# ShiftRegister.net
KiCad netlist of a schematic drawn in Altium Designer
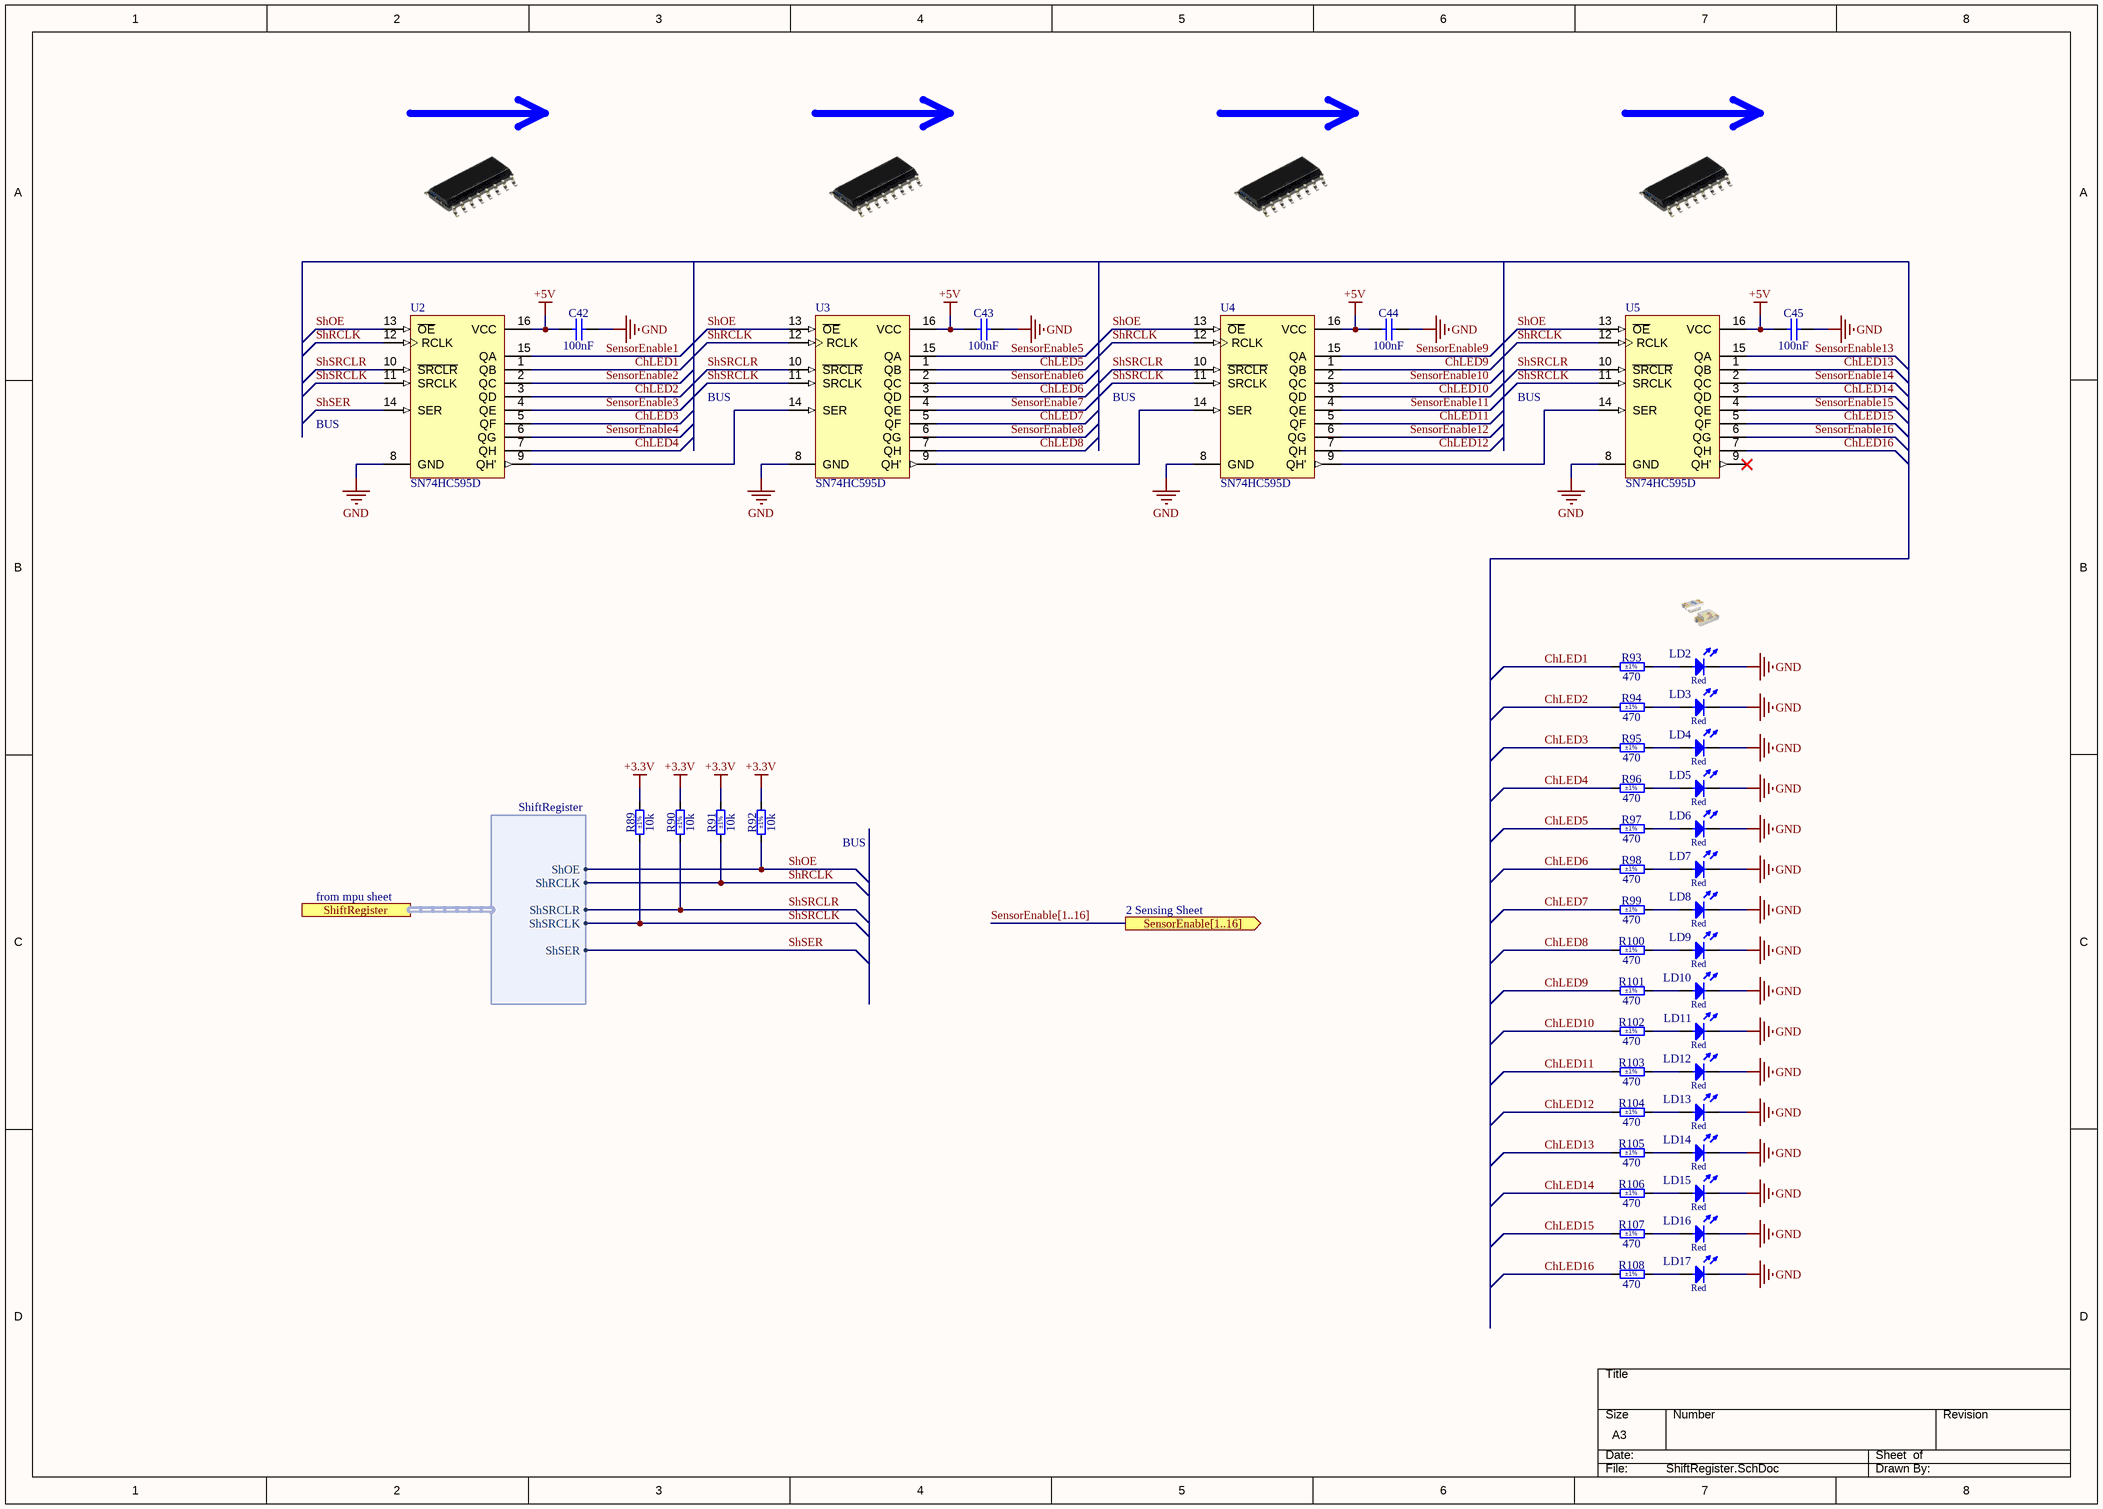
[diagram p0: ShiftRegister.SchDoc]

(export (version "E")
  (design (tool "Eeschema 10.0.6"))
  (components
    (comp (ref "C42")
      (value "100nF")
      (footprint "CAPC1608X87N")
      (description "Non-polarised capacitor")
      (fields
        (field (name "PART NUMBER") "CC0603_100NF_50V_10%_X7R")
        (field (name "VOLTAGE") "50V")
        (field (name "AUTHOR") "CERN DEM JLC")
      )
      (libsource (lib "Capacitors") (part "Capacitor - non polarized"))
    )
    (comp (ref "C43")
      (value "100nF")
      (footprint "CAPC1608X87N")
      (description "Non-polarised capacitor")
      (fields
        (field (name "PART NUMBER") "CC0603_100NF_50V_10%_X7R")
        (field (name "VOLTAGE") "50V")
        (field (name "AUTHOR") "CERN DEM JLC")
      )
      (libsource (lib "Capacitors") (part "Capacitor - non polarized"))
    )
    (comp (ref "C44")
      (value "100nF")
      (footprint "CAPC1608X87N")
      (description "Non-polarised capacitor")
      (fields
        (field (name "PART NUMBER") "CC0603_100NF_50V_10%_X7R")
        (field (name "VOLTAGE") "50V")
        (field (name "AUTHOR") "CERN DEM JLC")
      )
      (libsource (lib "Capacitors") (part "Capacitor - non polarized"))
    )
    (comp (ref "C45")
      (value "100nF")
      (footprint "CAPC1608X87N")
      (description "Non-polarised capacitor")
      (fields
        (field (name "PART NUMBER") "CC0603_100NF_50V_10%_X7R")
        (field (name "VOLTAGE") "50V")
        (field (name "AUTHOR") "CERN DEM JLC")
      )
      (libsource (lib "Capacitors") (part "Capacitor - non polarized"))
    )
    (comp (ref "LD2")
      (value "Red")
      (footprint "LED_AVAGO_HSMH-C150")
      (description "LED Red 1C 2A")
      (fields
        (field (name "PART NUMBER") "LED_AVAGO_HSMH-C150")
        (field (name "MANUFACTURER") "AVAGO TECHNOLOGIES")
        (field (name "AUTHOR") "CERN DEM JLC")
      )
      (libsource (lib "ICs And Semiconductors") (part "LED Red 1C 2A"))
    )
    (comp (ref "LD3")
      (value "Red")
      (footprint "LED_AVAGO_HSMH-C150")
      (description "LED Red 1C 2A")
      (fields
        (field (name "PART NUMBER") "LED_AVAGO_HSMH-C150")
        (field (name "MANUFACTURER") "AVAGO TECHNOLOGIES")
        (field (name "AUTHOR") "CERN DEM JLC")
      )
      (libsource (lib "ICs And Semiconductors") (part "LED Red 1C 2A"))
    )
    (comp (ref "LD4")
      (value "Red")
      (footprint "LED_AVAGO_HSMH-C150")
      (description "LED Red 1C 2A")
      (fields
        (field (name "PART NUMBER") "LED_AVAGO_HSMH-C150")
        (field (name "MANUFACTURER") "AVAGO TECHNOLOGIES")
        (field (name "AUTHOR") "CERN DEM JLC")
      )
      (libsource (lib "ICs And Semiconductors") (part "LED Red 1C 2A"))
    )
    (comp (ref "LD5")
      (value "Red")
      (footprint "LED_AVAGO_HSMH-C150")
      (description "LED Red 1C 2A")
      (fields
        (field (name "PART NUMBER") "LED_AVAGO_HSMH-C150")
        (field (name "MANUFACTURER") "AVAGO TECHNOLOGIES")
        (field (name "AUTHOR") "CERN DEM JLC")
      )
      (libsource (lib "ICs And Semiconductors") (part "LED Red 1C 2A"))
    )
    (comp (ref "LD6")
      (value "Red")
      (footprint "LED_AVAGO_HSMH-C150")
      (description "LED Red 1C 2A")
      (fields
        (field (name "PART NUMBER") "LED_AVAGO_HSMH-C150")
        (field (name "MANUFACTURER") "AVAGO TECHNOLOGIES")
        (field (name "AUTHOR") "CERN DEM JLC")
      )
      (libsource (lib "ICs And Semiconductors") (part "LED Red 1C 2A"))
    )
    (comp (ref "LD7")
      (value "Red")
      (footprint "LED_AVAGO_HSMH-C150")
      (description "LED Red 1C 2A")
      (fields
        (field (name "PART NUMBER") "LED_AVAGO_HSMH-C150")
        (field (name "MANUFACTURER") "AVAGO TECHNOLOGIES")
        (field (name "AUTHOR") "CERN DEM JLC")
      )
      (libsource (lib "ICs And Semiconductors") (part "LED Red 1C 2A"))
    )
    (comp (ref "LD8")
      (value "Red")
      (footprint "LED_AVAGO_HSMH-C150")
      (description "LED Red 1C 2A")
      (fields
        (field (name "PART NUMBER") "LED_AVAGO_HSMH-C150")
        (field (name "MANUFACTURER") "AVAGO TECHNOLOGIES")
        (field (name "AUTHOR") "CERN DEM JLC")
      )
      (libsource (lib "ICs And Semiconductors") (part "LED Red 1C 2A"))
    )
    (comp (ref "LD9")
      (value "Red")
      (footprint "LED_AVAGO_HSMH-C150")
      (description "LED Red 1C 2A")
      (fields
        (field (name "PART NUMBER") "LED_AVAGO_HSMH-C150")
        (field (name "MANUFACTURER") "AVAGO TECHNOLOGIES")
        (field (name "AUTHOR") "CERN DEM JLC")
      )
      (libsource (lib "ICs And Semiconductors") (part "LED Red 1C 2A"))
    )
    (comp (ref "LD10")
      (value "Red")
      (footprint "LED_AVAGO_HSMH-C150")
      (description "LED Red 1C 2A")
      (fields
        (field (name "PART NUMBER") "LED_AVAGO_HSMH-C150")
        (field (name "MANUFACTURER") "AVAGO TECHNOLOGIES")
        (field (name "AUTHOR") "CERN DEM JLC")
      )
      (libsource (lib "ICs And Semiconductors") (part "LED Red 1C 2A"))
    )
    (comp (ref "LD11")
      (value "Red")
      (footprint "LED_AVAGO_HSMH-C150")
      (description "LED Red 1C 2A")
      (fields
        (field (name "PART NUMBER") "LED_AVAGO_HSMH-C150")
        (field (name "MANUFACTURER") "AVAGO TECHNOLOGIES")
        (field (name "AUTHOR") "CERN DEM JLC")
      )
      (libsource (lib "ICs And Semiconductors") (part "LED Red 1C 2A"))
    )
    (comp (ref "LD12")
      (value "Red")
      (footprint "LED_AVAGO_HSMH-C150")
      (description "LED Red 1C 2A")
      (fields
        (field (name "PART NUMBER") "LED_AVAGO_HSMH-C150")
        (field (name "MANUFACTURER") "AVAGO TECHNOLOGIES")
        (field (name "AUTHOR") "CERN DEM JLC")
      )
      (libsource (lib "ICs And Semiconductors") (part "LED Red 1C 2A"))
    )
    (comp (ref "LD13")
      (value "Red")
      (footprint "LED_AVAGO_HSMH-C150")
      (description "LED Red 1C 2A")
      (fields
        (field (name "PART NUMBER") "LED_AVAGO_HSMH-C150")
        (field (name "MANUFACTURER") "AVAGO TECHNOLOGIES")
        (field (name "AUTHOR") "CERN DEM JLC")
      )
      (libsource (lib "ICs And Semiconductors") (part "LED Red 1C 2A"))
    )
    (comp (ref "LD14")
      (value "Red")
      (footprint "LED_AVAGO_HSMH-C150")
      (description "LED Red 1C 2A")
      (fields
        (field (name "PART NUMBER") "LED_AVAGO_HSMH-C150")
        (field (name "MANUFACTURER") "AVAGO TECHNOLOGIES")
        (field (name "AUTHOR") "CERN DEM JLC")
      )
      (libsource (lib "ICs And Semiconductors") (part "LED Red 1C 2A"))
    )
    (comp (ref "LD15")
      (value "Red")
      (footprint "LED_AVAGO_HSMH-C150")
      (description "LED Red 1C 2A")
      (fields
        (field (name "PART NUMBER") "LED_AVAGO_HSMH-C150")
        (field (name "MANUFACTURER") "AVAGO TECHNOLOGIES")
        (field (name "AUTHOR") "CERN DEM JLC")
      )
      (libsource (lib "ICs And Semiconductors") (part "LED Red 1C 2A"))
    )
    (comp (ref "LD16")
      (value "Red")
      (footprint "LED_AVAGO_HSMH-C150")
      (description "LED Red 1C 2A")
      (fields
        (field (name "PART NUMBER") "LED_AVAGO_HSMH-C150")
        (field (name "MANUFACTURER") "AVAGO TECHNOLOGIES")
        (field (name "AUTHOR") "CERN DEM JLC")
      )
      (libsource (lib "ICs And Semiconductors") (part "LED Red 1C 2A"))
    )
    (comp (ref "LD17")
      (value "Red")
      (footprint "LED_AVAGO_HSMH-C150")
      (description "LED Red 1C 2A")
      (fields
        (field (name "PART NUMBER") "LED_AVAGO_HSMH-C150")
        (field (name "MANUFACTURER") "AVAGO TECHNOLOGIES")
        (field (name "AUTHOR") "CERN DEM JLC")
      )
      (libsource (lib "ICs And Semiconductors") (part "LED Red 1C 2A"))
    )
    (comp (ref "R89")
      (value "10k")
      (footprint "RESC1608X55N")
      (description "Resistor - 1%")
      (fields
        (field (name "TOLERANCE") "±1%")
        (field (name "PART NUMBER") "R0603_10K_1%_0.1W_100PPM")
        (field (name "POWER") "0.1W")
        (field (name "AUTHOR") "CERN DEM JLC")
      )
      (libsource (lib "Resistors") (part "Resistor - 1%"))
    )
    (comp (ref "R90")
      (value "10k")
      (footprint "RESC1608X55N")
      (description "Resistor - 1%")
      (fields
        (field (name "TOLERANCE") "±1%")
        (field (name "PART NUMBER") "R0603_10K_1%_0.1W_100PPM")
        (field (name "POWER") "0.1W")
        (field (name "AUTHOR") "CERN DEM JLC")
      )
      (libsource (lib "Resistors") (part "Resistor - 1%"))
    )
    (comp (ref "R91")
      (value "10k")
      (footprint "RESC1608X55N")
      (description "Resistor - 1%")
      (fields
        (field (name "TOLERANCE") "±1%")
        (field (name "PART NUMBER") "R0603_10K_1%_0.1W_100PPM")
        (field (name "POWER") "0.1W")
        (field (name "AUTHOR") "CERN DEM JLC")
      )
      (libsource (lib "Resistors") (part "Resistor - 1%"))
    )
    (comp (ref "R92")
      (value "10k")
      (footprint "RESC1608X55N")
      (description "Resistor - 1%")
      (fields
        (field (name "TOLERANCE") "±1%")
        (field (name "PART NUMBER") "R0603_10K_1%_0.1W_100PPM")
        (field (name "POWER") "0.1W")
        (field (name "AUTHOR") "CERN DEM JLC")
      )
      (libsource (lib "Resistors") (part "Resistor - 1%"))
    )
    (comp (ref "R93")
      (value "470")
      (footprint "RESC1608X55N")
      (description "Resistor - 1%")
      (fields
        (field (name "TOLERANCE") "±1%")
        (field (name "PART NUMBER") "R0603_470R_1%_0.1W_100PPM")
        (field (name "POWER") "0.1W")
        (field (name "AUTHOR") "CERN DEM JLC")
      )
      (libsource (lib "Resistors") (part "Resistor - 1%"))
    )
    (comp (ref "R94")
      (value "470")
      (footprint "RESC1608X55N")
      (description "Resistor - 1%")
      (fields
        (field (name "TOLERANCE") "±1%")
        (field (name "PART NUMBER") "R0603_470R_1%_0.1W_100PPM")
        (field (name "POWER") "0.1W")
        (field (name "AUTHOR") "CERN DEM JLC")
      )
      (libsource (lib "Resistors") (part "Resistor - 1%"))
    )
    (comp (ref "R95")
      (value "470")
      (footprint "RESC1608X55N")
      (description "Resistor - 1%")
      (fields
        (field (name "TOLERANCE") "±1%")
        (field (name "PART NUMBER") "R0603_470R_1%_0.1W_100PPM")
        (field (name "POWER") "0.1W")
        (field (name "AUTHOR") "CERN DEM JLC")
      )
      (libsource (lib "Resistors") (part "Resistor - 1%"))
    )
    (comp (ref "R96")
      (value "470")
      (footprint "RESC1608X55N")
      (description "Resistor - 1%")
      (fields
        (field (name "TOLERANCE") "±1%")
        (field (name "PART NUMBER") "R0603_470R_1%_0.1W_100PPM")
        (field (name "POWER") "0.1W")
        (field (name "AUTHOR") "CERN DEM JLC")
      )
      (libsource (lib "Resistors") (part "Resistor - 1%"))
    )
    (comp (ref "R97")
      (value "470")
      (footprint "RESC1608X55N")
      (description "Resistor - 1%")
      (fields
        (field (name "TOLERANCE") "±1%")
        (field (name "PART NUMBER") "R0603_470R_1%_0.1W_100PPM")
        (field (name "POWER") "0.1W")
        (field (name "AUTHOR") "CERN DEM JLC")
      )
      (libsource (lib "Resistors") (part "Resistor - 1%"))
    )
    (comp (ref "R98")
      (value "470")
      (footprint "RESC1608X55N")
      (description "Resistor - 1%")
      (fields
        (field (name "TOLERANCE") "±1%")
        (field (name "PART NUMBER") "R0603_470R_1%_0.1W_100PPM")
        (field (name "POWER") "0.1W")
        (field (name "AUTHOR") "CERN DEM JLC")
      )
      (libsource (lib "Resistors") (part "Resistor - 1%"))
    )
    (comp (ref "R99")
      (value "470")
      (footprint "RESC1608X55N")
      (description "Resistor - 1%")
      (fields
        (field (name "TOLERANCE") "±1%")
        (field (name "PART NUMBER") "R0603_470R_1%_0.1W_100PPM")
        (field (name "POWER") "0.1W")
        (field (name "AUTHOR") "CERN DEM JLC")
      )
      (libsource (lib "Resistors") (part "Resistor - 1%"))
    )
    (comp (ref "R100")
      (value "470")
      (footprint "RESC1608X55N")
      (description "Resistor - 1%")
      (fields
        (field (name "TOLERANCE") "±1%")
        (field (name "PART NUMBER") "R0603_470R_1%_0.1W_100PPM")
        (field (name "POWER") "0.1W")
        (field (name "AUTHOR") "CERN DEM JLC")
      )
      (libsource (lib "Resistors") (part "Resistor - 1%"))
    )
    (comp (ref "R101")
      (value "470")
      (footprint "RESC1608X55N")
      (description "Resistor - 1%")
      (fields
        (field (name "TOLERANCE") "±1%")
        (field (name "PART NUMBER") "R0603_470R_1%_0.1W_100PPM")
        (field (name "POWER") "0.1W")
        (field (name "AUTHOR") "CERN DEM JLC")
      )
      (libsource (lib "Resistors") (part "Resistor - 1%"))
    )
    (comp (ref "R102")
      (value "470")
      (footprint "RESC1608X55N")
      (description "Resistor - 1%")
      (fields
        (field (name "TOLERANCE") "±1%")
        (field (name "PART NUMBER") "R0603_470R_1%_0.1W_100PPM")
        (field (name "POWER") "0.1W")
        (field (name "AUTHOR") "CERN DEM JLC")
      )
      (libsource (lib "Resistors") (part "Resistor - 1%"))
    )
    (comp (ref "R103")
      (value "470")
      (footprint "RESC1608X55N")
      (description "Resistor - 1%")
      (fields
        (field (name "TOLERANCE") "±1%")
        (field (name "PART NUMBER") "R0603_470R_1%_0.1W_100PPM")
        (field (name "POWER") "0.1W")
        (field (name "AUTHOR") "CERN DEM JLC")
      )
      (libsource (lib "Resistors") (part "Resistor - 1%"))
    )
    (comp (ref "R104")
      (value "470")
      (footprint "RESC1608X55N")
      (description "Resistor - 1%")
      (fields
        (field (name "TOLERANCE") "±1%")
        (field (name "PART NUMBER") "R0603_470R_1%_0.1W_100PPM")
        (field (name "POWER") "0.1W")
        (field (name "AUTHOR") "CERN DEM JLC")
      )
      (libsource (lib "Resistors") (part "Resistor - 1%"))
    )
    (comp (ref "R105")
      (value "470")
      (footprint "RESC1608X55N")
      (description "Resistor - 1%")
      (fields
        (field (name "TOLERANCE") "±1%")
        (field (name "PART NUMBER") "R0603_470R_1%_0.1W_100PPM")
        (field (name "POWER") "0.1W")
        (field (name "AUTHOR") "CERN DEM JLC")
      )
      (libsource (lib "Resistors") (part "Resistor - 1%"))
    )
    (comp (ref "R106")
      (value "470")
      (footprint "RESC1608X55N")
      (description "Resistor - 1%")
      (fields
        (field (name "TOLERANCE") "±1%")
        (field (name "PART NUMBER") "R0603_470R_1%_0.1W_100PPM")
        (field (name "POWER") "0.1W")
        (field (name "AUTHOR") "CERN DEM JLC")
      )
      (libsource (lib "Resistors") (part "Resistor - 1%"))
    )
    (comp (ref "R107")
      (value "470")
      (footprint "RESC1608X55N")
      (description "Resistor - 1%")
      (fields
        (field (name "TOLERANCE") "±1%")
        (field (name "PART NUMBER") "R0603_470R_1%_0.1W_100PPM")
        (field (name "POWER") "0.1W")
        (field (name "AUTHOR") "CERN DEM JLC")
      )
      (libsource (lib "Resistors") (part "Resistor - 1%"))
    )
    (comp (ref "R108")
      (value "470")
      (footprint "RESC1608X55N")
      (description "Resistor - 1%")
      (fields
        (field (name "TOLERANCE") "±1%")
        (field (name "PART NUMBER") "R0603_470R_1%_0.1W_100PPM")
        (field (name "POWER") "0.1W")
        (field (name "AUTHOR") "CERN DEM JLC")
      )
      (libsource (lib "Resistors") (part "Resistor - 1%"))
    )
    (comp (ref "U2")
      (value "SN74HC595D")
      (footprint "SO16")
      (description "8-Bit Shift Register with 3-State Output Registers")
      (fields (field (name "PUBLISHER") "Altium Limited"))
      (libsource (lib "Sajad_Altium_Library") (part "SN74HC595D"))
    )
    (comp (ref "U3")
      (value "SN74HC595D")
      (footprint "SO16")
      (description "8-Bit Shift Register with 3-State Output Registers")
      (fields (field (name "PUBLISHER") "Altium Limited"))
      (libsource (lib "Sajad_Altium_Library") (part "SN74HC595D"))
    )
    (comp (ref "U4")
      (value "SN74HC595D")
      (footprint "SO16")
      (description "8-Bit Shift Register with 3-State Output Registers")
      (fields (field (name "PUBLISHER") "Altium Limited"))
      (libsource (lib "Sajad_Altium_Library") (part "SN74HC595D"))
    )
    (comp (ref "U5")
      (value "SN74HC595D")
      (footprint "SO16")
      (description "8-Bit Shift Register with 3-State Output Registers")
      (fields (field (name "PUBLISHER") "Altium Limited"))
      (libsource (lib "Sajad_Altium_Library") (part "SN74HC595D"))
    )
  )
  (nets
    (net (code "2") (name "+3.3V") (class "Default")
      (node (ref "R89") (pin "2") (pinfunction "2_2") (pintype "passive"))
      (node (ref "R90") (pin "2") (pinfunction "2_2") (pintype "passive"))
      (node (ref "R91") (pin "2") (pinfunction "2_2") (pintype "passive"))
      (node (ref "R92") (pin "2") (pinfunction "2_2") (pintype "passive"))
    )
    (net (code "3") (name "+5V") (class "Default")
      (node (ref "C42") (pin "1") (pinfunction "1_1") (pintype "passive"))
      (node (ref "C43") (pin "1") (pinfunction "1_1") (pintype "passive"))
      (node (ref "C44") (pin "1") (pinfunction "1_1") (pintype "passive"))
      (node (ref "C45") (pin "1") (pinfunction "1_1") (pintype "passive"))
      (node (ref "U2") (pin "16") (pinfunction "VCC_16") (pintype "power_in"))
      (node (ref "U3") (pin "16") (pinfunction "VCC_16") (pintype "power_in"))
      (node (ref "U4") (pin "16") (pinfunction "VCC_16") (pintype "power_in"))
      (node (ref "U5") (pin "16") (pinfunction "VCC_16") (pintype "power_in"))
    )
    (net (code "4") (name "/ChLED1") (class "Default")
      (node (ref "R93") (pin "1") (pinfunction "1_1") (pintype "passive"))
      (node (ref "U2") (pin "1") (pinfunction "QB_1") (pintype "tri_state"))
    )
    (net (code "5") (name "/ChLED2") (class "Default")
      (node (ref "R94") (pin "1") (pinfunction "1_1") (pintype "passive"))
      (node (ref "U2") (pin "3") (pinfunction "QD_3") (pintype "tri_state"))
    )
    (net (code "6") (name "/ChLED3") (class "Default")
      (node (ref "R95") (pin "1") (pinfunction "1_1") (pintype "passive"))
      (node (ref "U2") (pin "5") (pinfunction "QF_5") (pintype "tri_state"))
    )
    (net (code "7") (name "/ChLED4") (class "Default")
      (node (ref "R96") (pin "1") (pinfunction "1_1") (pintype "passive"))
      (node (ref "U2") (pin "7") (pinfunction "QH_7") (pintype "tri_state"))
    )
    (net (code "8") (name "/ChLED5") (class "Default")
      (node (ref "R97") (pin "1") (pinfunction "1_1") (pintype "passive"))
      (node (ref "U3") (pin "1") (pinfunction "QB_1") (pintype "tri_state"))
    )
    (net (code "9") (name "/ChLED6") (class "Default")
      (node (ref "R98") (pin "1") (pinfunction "1_1") (pintype "passive"))
      (node (ref "U3") (pin "3") (pinfunction "QD_3") (pintype "tri_state"))
    )
    (net (code "10") (name "/ChLED7") (class "Default")
      (node (ref "R99") (pin "1") (pinfunction "1_1") (pintype "passive"))
      (node (ref "U3") (pin "5") (pinfunction "QF_5") (pintype "tri_state"))
    )
    (net (code "11") (name "/ChLED8") (class "Default")
      (node (ref "R100") (pin "1") (pinfunction "1_1") (pintype "passive"))
      (node (ref "U3") (pin "7") (pinfunction "QH_7") (pintype "tri_state"))
    )
    (net (code "12") (name "/ChLED9") (class "Default")
      (node (ref "R101") (pin "1") (pinfunction "1_1") (pintype "passive"))
      (node (ref "U4") (pin "1") (pinfunction "QB_1") (pintype "tri_state"))
    )
    (net (code "13") (name "/ChLED10") (class "Default")
      (node (ref "R102") (pin "1") (pinfunction "1_1") (pintype "passive"))
      (node (ref "U4") (pin "3") (pinfunction "QD_3") (pintype "tri_state"))
    )
    (net (code "14") (name "/ChLED11") (class "Default")
      (node (ref "R103") (pin "1") (pinfunction "1_1") (pintype "passive"))
      (node (ref "U4") (pin "5") (pinfunction "QF_5") (pintype "tri_state"))
    )
    (net (code "15") (name "/ChLED12") (class "Default")
      (node (ref "R104") (pin "1") (pinfunction "1_1") (pintype "passive"))
      (node (ref "U4") (pin "7") (pinfunction "QH_7") (pintype "tri_state"))
    )
    (net (code "16") (name "/ChLED13") (class "Default")
      (node (ref "R105") (pin "1") (pinfunction "1_1") (pintype "passive"))
      (node (ref "U5") (pin "1") (pinfunction "QB_1") (pintype "tri_state"))
    )
    (net (code "17") (name "/ChLED14") (class "Default")
      (node (ref "R106") (pin "1") (pinfunction "1_1") (pintype "passive"))
      (node (ref "U5") (pin "3") (pinfunction "QD_3") (pintype "tri_state"))
    )
    (net (code "18") (name "/ChLED15") (class "Default")
      (node (ref "R107") (pin "1") (pinfunction "1_1") (pintype "passive"))
      (node (ref "U5") (pin "5") (pinfunction "QF_5") (pintype "tri_state"))
    )
    (net (code "19") (name "/ChLED16") (class "Default")
      (node (ref "R108") (pin "1") (pinfunction "1_1") (pintype "passive"))
      (node (ref "U5") (pin "7") (pinfunction "QH_7") (pintype "tri_state"))
    )
    (net (code "20") (name "/SensorEnable1") (class "Default")
      (node (ref "U2") (pin "15") (pinfunction "QA_15") (pintype "tri_state"))
    )
    (net (code "21") (name "/SensorEnable2") (class "Default")
      (node (ref "U2") (pin "2") (pinfunction "QC_2") (pintype "tri_state"))
    )
    (net (code "22") (name "/SensorEnable3") (class "Default")
      (node (ref "U2") (pin "4") (pinfunction "QE_4") (pintype "tri_state"))
    )
    (net (code "23") (name "/SensorEnable4") (class "Default")
      (node (ref "U2") (pin "6") (pinfunction "QG_6") (pintype "tri_state"))
    )
    (net (code "24") (name "/SensorEnable5") (class "Default")
      (node (ref "U3") (pin "15") (pinfunction "QA_15") (pintype "tri_state"))
    )
    (net (code "25") (name "/SensorEnable6") (class "Default")
      (node (ref "U3") (pin "2") (pinfunction "QC_2") (pintype "tri_state"))
    )
    (net (code "26") (name "/SensorEnable7") (class "Default")
      (node (ref "U3") (pin "4") (pinfunction "QE_4") (pintype "tri_state"))
    )
    (net (code "27") (name "/SensorEnable8") (class "Default")
      (node (ref "U3") (pin "6") (pinfunction "QG_6") (pintype "tri_state"))
    )
    (net (code "28") (name "/SensorEnable9") (class "Default")
      (node (ref "U4") (pin "15") (pinfunction "QA_15") (pintype "tri_state"))
    )
    (net (code "29") (name "/SensorEnable10") (class "Default")
      (node (ref "U4") (pin "2") (pinfunction "QC_2") (pintype "tri_state"))
    )
    (net (code "30") (name "/SensorEnable11") (class "Default")
      (node (ref "U4") (pin "4") (pinfunction "QE_4") (pintype "tri_state"))
    )
    (net (code "31") (name "/SensorEnable12") (class "Default")
      (node (ref "U4") (pin "6") (pinfunction "QG_6") (pintype "tri_state"))
    )
    (net (code "32") (name "/SensorEnable13") (class "Default")
      (node (ref "U5") (pin "15") (pinfunction "QA_15") (pintype "tri_state"))
    )
    (net (code "33") (name "/SensorEnable14") (class "Default")
      (node (ref "U5") (pin "2") (pinfunction "QC_2") (pintype "tri_state"))
    )
    (net (code "34") (name "/SensorEnable15") (class "Default")
      (node (ref "U5") (pin "4") (pinfunction "QE_4") (pintype "tri_state"))
    )
    (net (code "35") (name "/SensorEnable16") (class "Default")
      (node (ref "U5") (pin "6") (pinfunction "QG_6") (pintype "tri_state"))
    )
    (net (code "37") (name "/ShOE") (class "Default")
      (node (ref "R92") (pin "1") (pinfunction "1_1") (pintype "passive"))
      (node (ref "U2") (pin "13") (pinfunction "~{OE}_13") (pintype "input"))
      (node (ref "U3") (pin "13") (pinfunction "~{OE}_13") (pintype "input"))
      (node (ref "U4") (pin "13") (pinfunction "~{OE}_13") (pintype "input"))
      (node (ref "U5") (pin "13") (pinfunction "~{OE}_13") (pintype "input"))
    )
    (net (code "38") (name "/ShRCLK") (class "Default")
      (node (ref "R91") (pin "1") (pinfunction "1_1") (pintype "passive"))
      (node (ref "U2") (pin "12") (pinfunction "RCLK_12") (pintype "input"))
      (node (ref "U3") (pin "12") (pinfunction "RCLK_12") (pintype "input"))
      (node (ref "U4") (pin "12") (pinfunction "RCLK_12") (pintype "input"))
      (node (ref "U5") (pin "12") (pinfunction "RCLK_12") (pintype "input"))
    )
    (net (code "39") (name "/ShSER") (class "Default")
      (node (ref "U2") (pin "14") (pinfunction "SER_14") (pintype "input"))
    )
    (net (code "40") (name "/ShSRCLK") (class "Default")
      (node (ref "R89") (pin "1") (pinfunction "1_1") (pintype "passive"))
      (node (ref "U2") (pin "11") (pinfunction "SRCLK_11") (pintype "input"))
      (node (ref "U3") (pin "11") (pinfunction "SRCLK_11") (pintype "input"))
      (node (ref "U4") (pin "11") (pinfunction "SRCLK_11") (pintype "input"))
      (node (ref "U5") (pin "11") (pinfunction "SRCLK_11") (pintype "input"))
    )
    (net (code "41") (name "/ShSRCLR") (class "Default")
      (node (ref "R90") (pin "1") (pinfunction "1_1") (pintype "passive"))
      (node (ref "U2") (pin "10") (pinfunction "~{SRCLR}_10") (pintype "input"))
      (node (ref "U3") (pin "10") (pinfunction "~{SRCLR}_10") (pintype "input"))
      (node (ref "U4") (pin "10") (pinfunction "~{SRCLR}_10") (pintype "input"))
      (node (ref "U5") (pin "10") (pinfunction "~{SRCLR}_10") (pintype "input"))
    )
    (net (code "43") (name "GND") (class "Default")
      (node (ref "C42") (pin "2") (pinfunction "2_2") (pintype "passive"))
      (node (ref "C43") (pin "2") (pinfunction "2_2") (pintype "passive"))
      (node (ref "C44") (pin "2") (pinfunction "2_2") (pintype "passive"))
      (node (ref "C45") (pin "2") (pinfunction "2_2") (pintype "passive"))
      (node (ref "LD10") (pin "1") (pinfunction "C_1") (pintype "passive"))
      (node (ref "LD11") (pin "1") (pinfunction "C_1") (pintype "passive"))
      (node (ref "LD12") (pin "1") (pinfunction "C_1") (pintype "passive"))
      (node (ref "LD13") (pin "1") (pinfunction "C_1") (pintype "passive"))
      (node (ref "LD14") (pin "1") (pinfunction "C_1") (pintype "passive"))
      (node (ref "LD15") (pin "1") (pinfunction "C_1") (pintype "passive"))
      (node (ref "LD16") (pin "1") (pinfunction "C_1") (pintype "passive"))
      (node (ref "LD17") (pin "1") (pinfunction "C_1") (pintype "passive"))
      (node (ref "LD2") (pin "1") (pinfunction "C_1") (pintype "passive"))
      (node (ref "LD3") (pin "1") (pinfunction "C_1") (pintype "passive"))
      (node (ref "LD4") (pin "1") (pinfunction "C_1") (pintype "passive"))
      (node (ref "LD5") (pin "1") (pinfunction "C_1") (pintype "passive"))
      (node (ref "LD6") (pin "1") (pinfunction "C_1") (pintype "passive"))
      (node (ref "LD7") (pin "1") (pinfunction "C_1") (pintype "passive"))
      (node (ref "LD8") (pin "1") (pinfunction "C_1") (pintype "passive"))
      (node (ref "LD9") (pin "1") (pinfunction "C_1") (pintype "passive"))
      (node (ref "U2") (pin "8") (pinfunction "GND_8") (pintype "power_in"))
      (node (ref "U3") (pin "8") (pinfunction "GND_8") (pintype "power_in"))
      (node (ref "U4") (pin "8") (pinfunction "GND_8") (pintype "power_in"))
      (node (ref "U5") (pin "8") (pinfunction "GND_8") (pintype "power_in"))
    )
    (net (code "44") (name "Net-(LD2-A)") (class "Default")
      (node (ref "LD2") (pin "2") (pinfunction "A_2") (pintype "passive"))
      (node (ref "R93") (pin "2") (pinfunction "2_2") (pintype "passive"))
    )
    (net (code "45") (name "Net-(LD3-A)") (class "Default")
      (node (ref "LD3") (pin "2") (pinfunction "A_2") (pintype "passive"))
      (node (ref "R94") (pin "2") (pinfunction "2_2") (pintype "passive"))
    )
    (net (code "46") (name "Net-(LD4-A)") (class "Default")
      (node (ref "LD4") (pin "2") (pinfunction "A_2") (pintype "passive"))
      (node (ref "R95") (pin "2") (pinfunction "2_2") (pintype "passive"))
    )
    (net (code "47") (name "Net-(LD5-A)") (class "Default")
      (node (ref "LD5") (pin "2") (pinfunction "A_2") (pintype "passive"))
      (node (ref "R96") (pin "2") (pinfunction "2_2") (pintype "passive"))
    )
    (net (code "48") (name "Net-(LD6-A)") (class "Default")
      (node (ref "LD6") (pin "2") (pinfunction "A_2") (pintype "passive"))
      (node (ref "R97") (pin "2") (pinfunction "2_2") (pintype "passive"))
    )
    (net (code "49") (name "Net-(LD7-A)") (class "Default")
      (node (ref "LD7") (pin "2") (pinfunction "A_2") (pintype "passive"))
      (node (ref "R98") (pin "2") (pinfunction "2_2") (pintype "passive"))
    )
    (net (code "50") (name "Net-(LD8-A)") (class "Default")
      (node (ref "LD8") (pin "2") (pinfunction "A_2") (pintype "passive"))
      (node (ref "R99") (pin "2") (pinfunction "2_2") (pintype "passive"))
    )
    (net (code "51") (name "Net-(LD9-A)") (class "Default")
      (node (ref "LD9") (pin "2") (pinfunction "A_2") (pintype "passive"))
      (node (ref "R100") (pin "2") (pinfunction "2_2") (pintype "passive"))
    )
    (net (code "52") (name "Net-(LD10-A)") (class "Default")
      (node (ref "LD10") (pin "2") (pinfunction "A_2") (pintype "passive"))
      (node (ref "R101") (pin "2") (pinfunction "2_2") (pintype "passive"))
    )
    (net (code "53") (name "Net-(LD11-A)") (class "Default")
      (node (ref "LD11") (pin "2") (pinfunction "A_2") (pintype "passive"))
      (node (ref "R102") (pin "2") (pinfunction "2_2") (pintype "passive"))
    )
    (net (code "54") (name "Net-(LD12-A)") (class "Default")
      (node (ref "LD12") (pin "2") (pinfunction "A_2") (pintype "passive"))
      (node (ref "R103") (pin "2") (pinfunction "2_2") (pintype "passive"))
    )
    (net (code "55") (name "Net-(LD13-A)") (class "Default")
      (node (ref "LD13") (pin "2") (pinfunction "A_2") (pintype "passive"))
      (node (ref "R104") (pin "2") (pinfunction "2_2") (pintype "passive"))
    )
    (net (code "56") (name "Net-(LD14-A)") (class "Default")
      (node (ref "LD14") (pin "2") (pinfunction "A_2") (pintype "passive"))
      (node (ref "R105") (pin "2") (pinfunction "2_2") (pintype "passive"))
    )
    (net (code "57") (name "Net-(LD15-A)") (class "Default")
      (node (ref "LD15") (pin "2") (pinfunction "A_2") (pintype "passive"))
      (node (ref "R106") (pin "2") (pinfunction "2_2") (pintype "passive"))
    )
    (net (code "58") (name "Net-(LD16-A)") (class "Default")
      (node (ref "LD16") (pin "2") (pinfunction "A_2") (pintype "passive"))
      (node (ref "R107") (pin "2") (pinfunction "2_2") (pintype "passive"))
    )
    (net (code "59") (name "Net-(LD17-A)") (class "Default")
      (node (ref "LD17") (pin "2") (pinfunction "A_2") (pintype "passive"))
      (node (ref "R108") (pin "2") (pinfunction "2_2") (pintype "passive"))
    )
    (net (code "60") (name "Net-(U2-QH')") (class "Default")
      (node (ref "U2") (pin "9") (pinfunction "QH'_9") (pintype "output"))
      (node (ref "U3") (pin "14") (pinfunction "SER_14") (pintype "input"))
    )
    (net (code "61") (name "Net-(U3-QH')") (class "Default")
      (node (ref "U3") (pin "9") (pinfunction "QH'_9") (pintype "output"))
      (node (ref "U4") (pin "14") (pinfunction "SER_14") (pintype "input"))
    )
    (net (code "62") (name "Net-(U4-QH')") (class "Default")
      (node (ref "U4") (pin "9") (pinfunction "QH'_9") (pintype "output"))
      (node (ref "U5") (pin "14") (pinfunction "SER_14") (pintype "input"))
    )
    (net (code "63") (name "unconnected-(U5-QH'-Pad9)") (class "Default")
      (node (ref "U5") (pin "9") (pinfunction "QH'_9") (pintype "output+no_connect"))
    )
  )
)
